# SCH_stewart-platform.net
KiCad netlist of a schematic drawn in EasyEDA
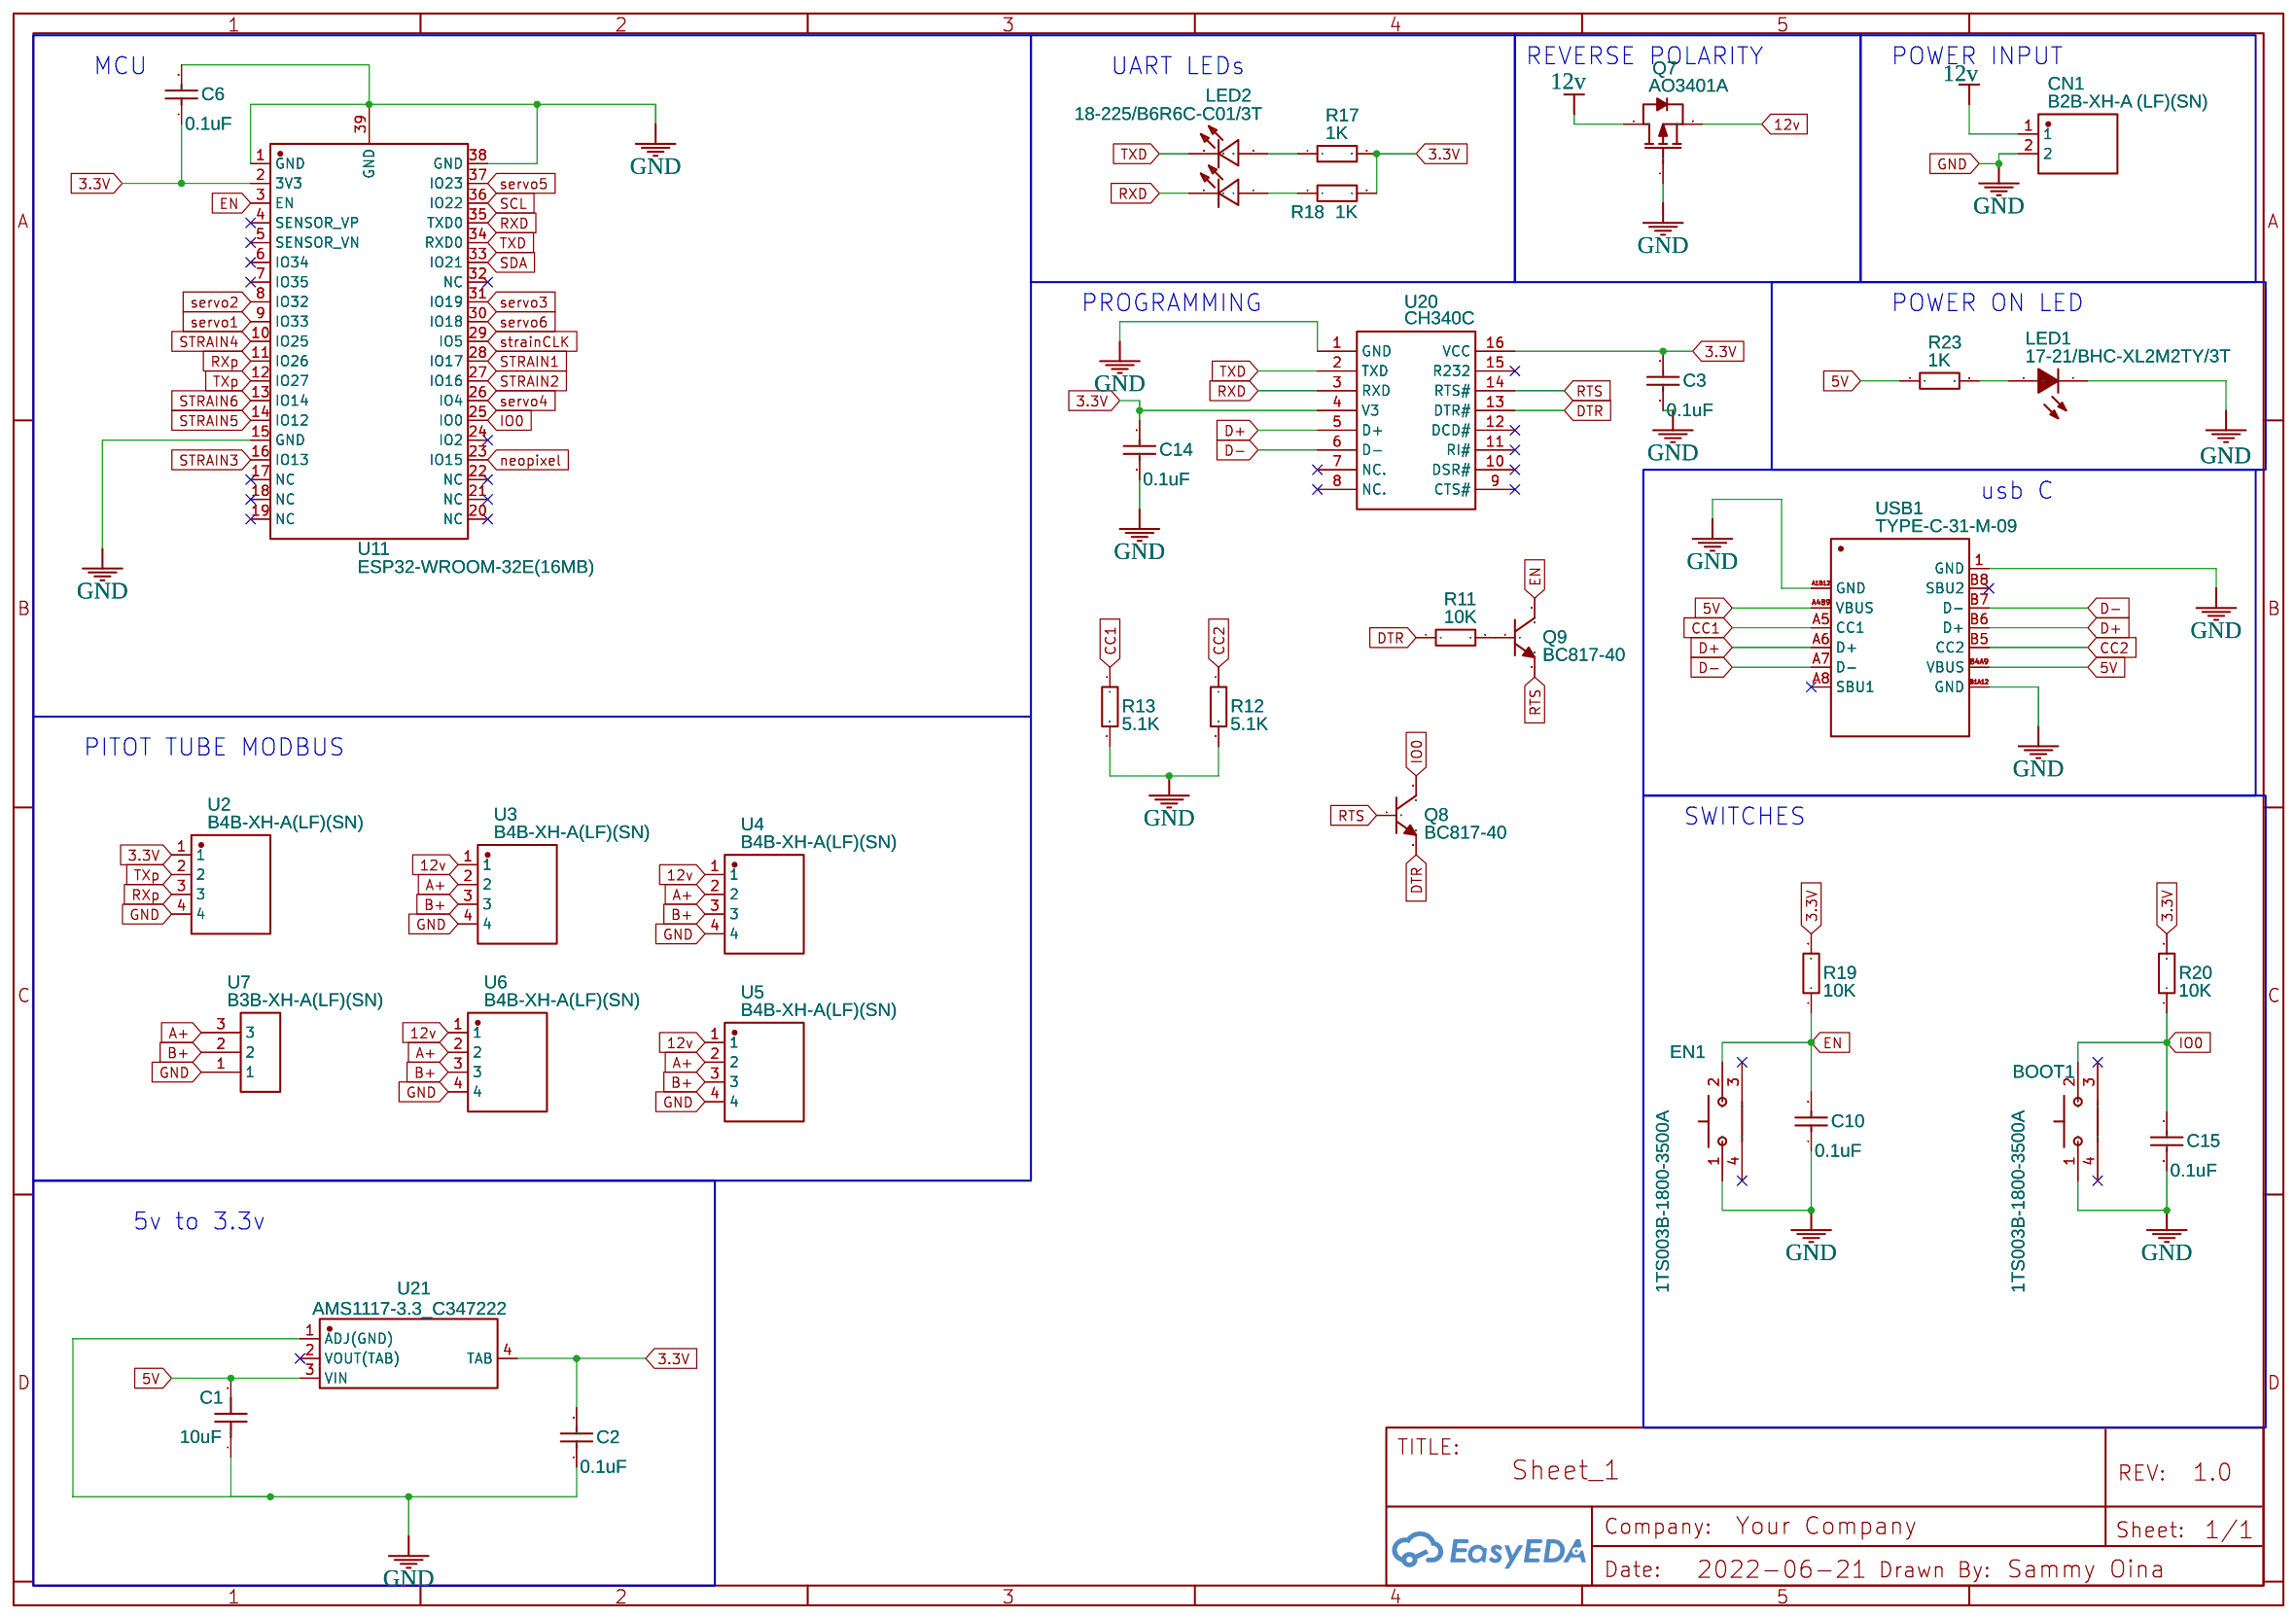
[diagram p0: Sheet_1]
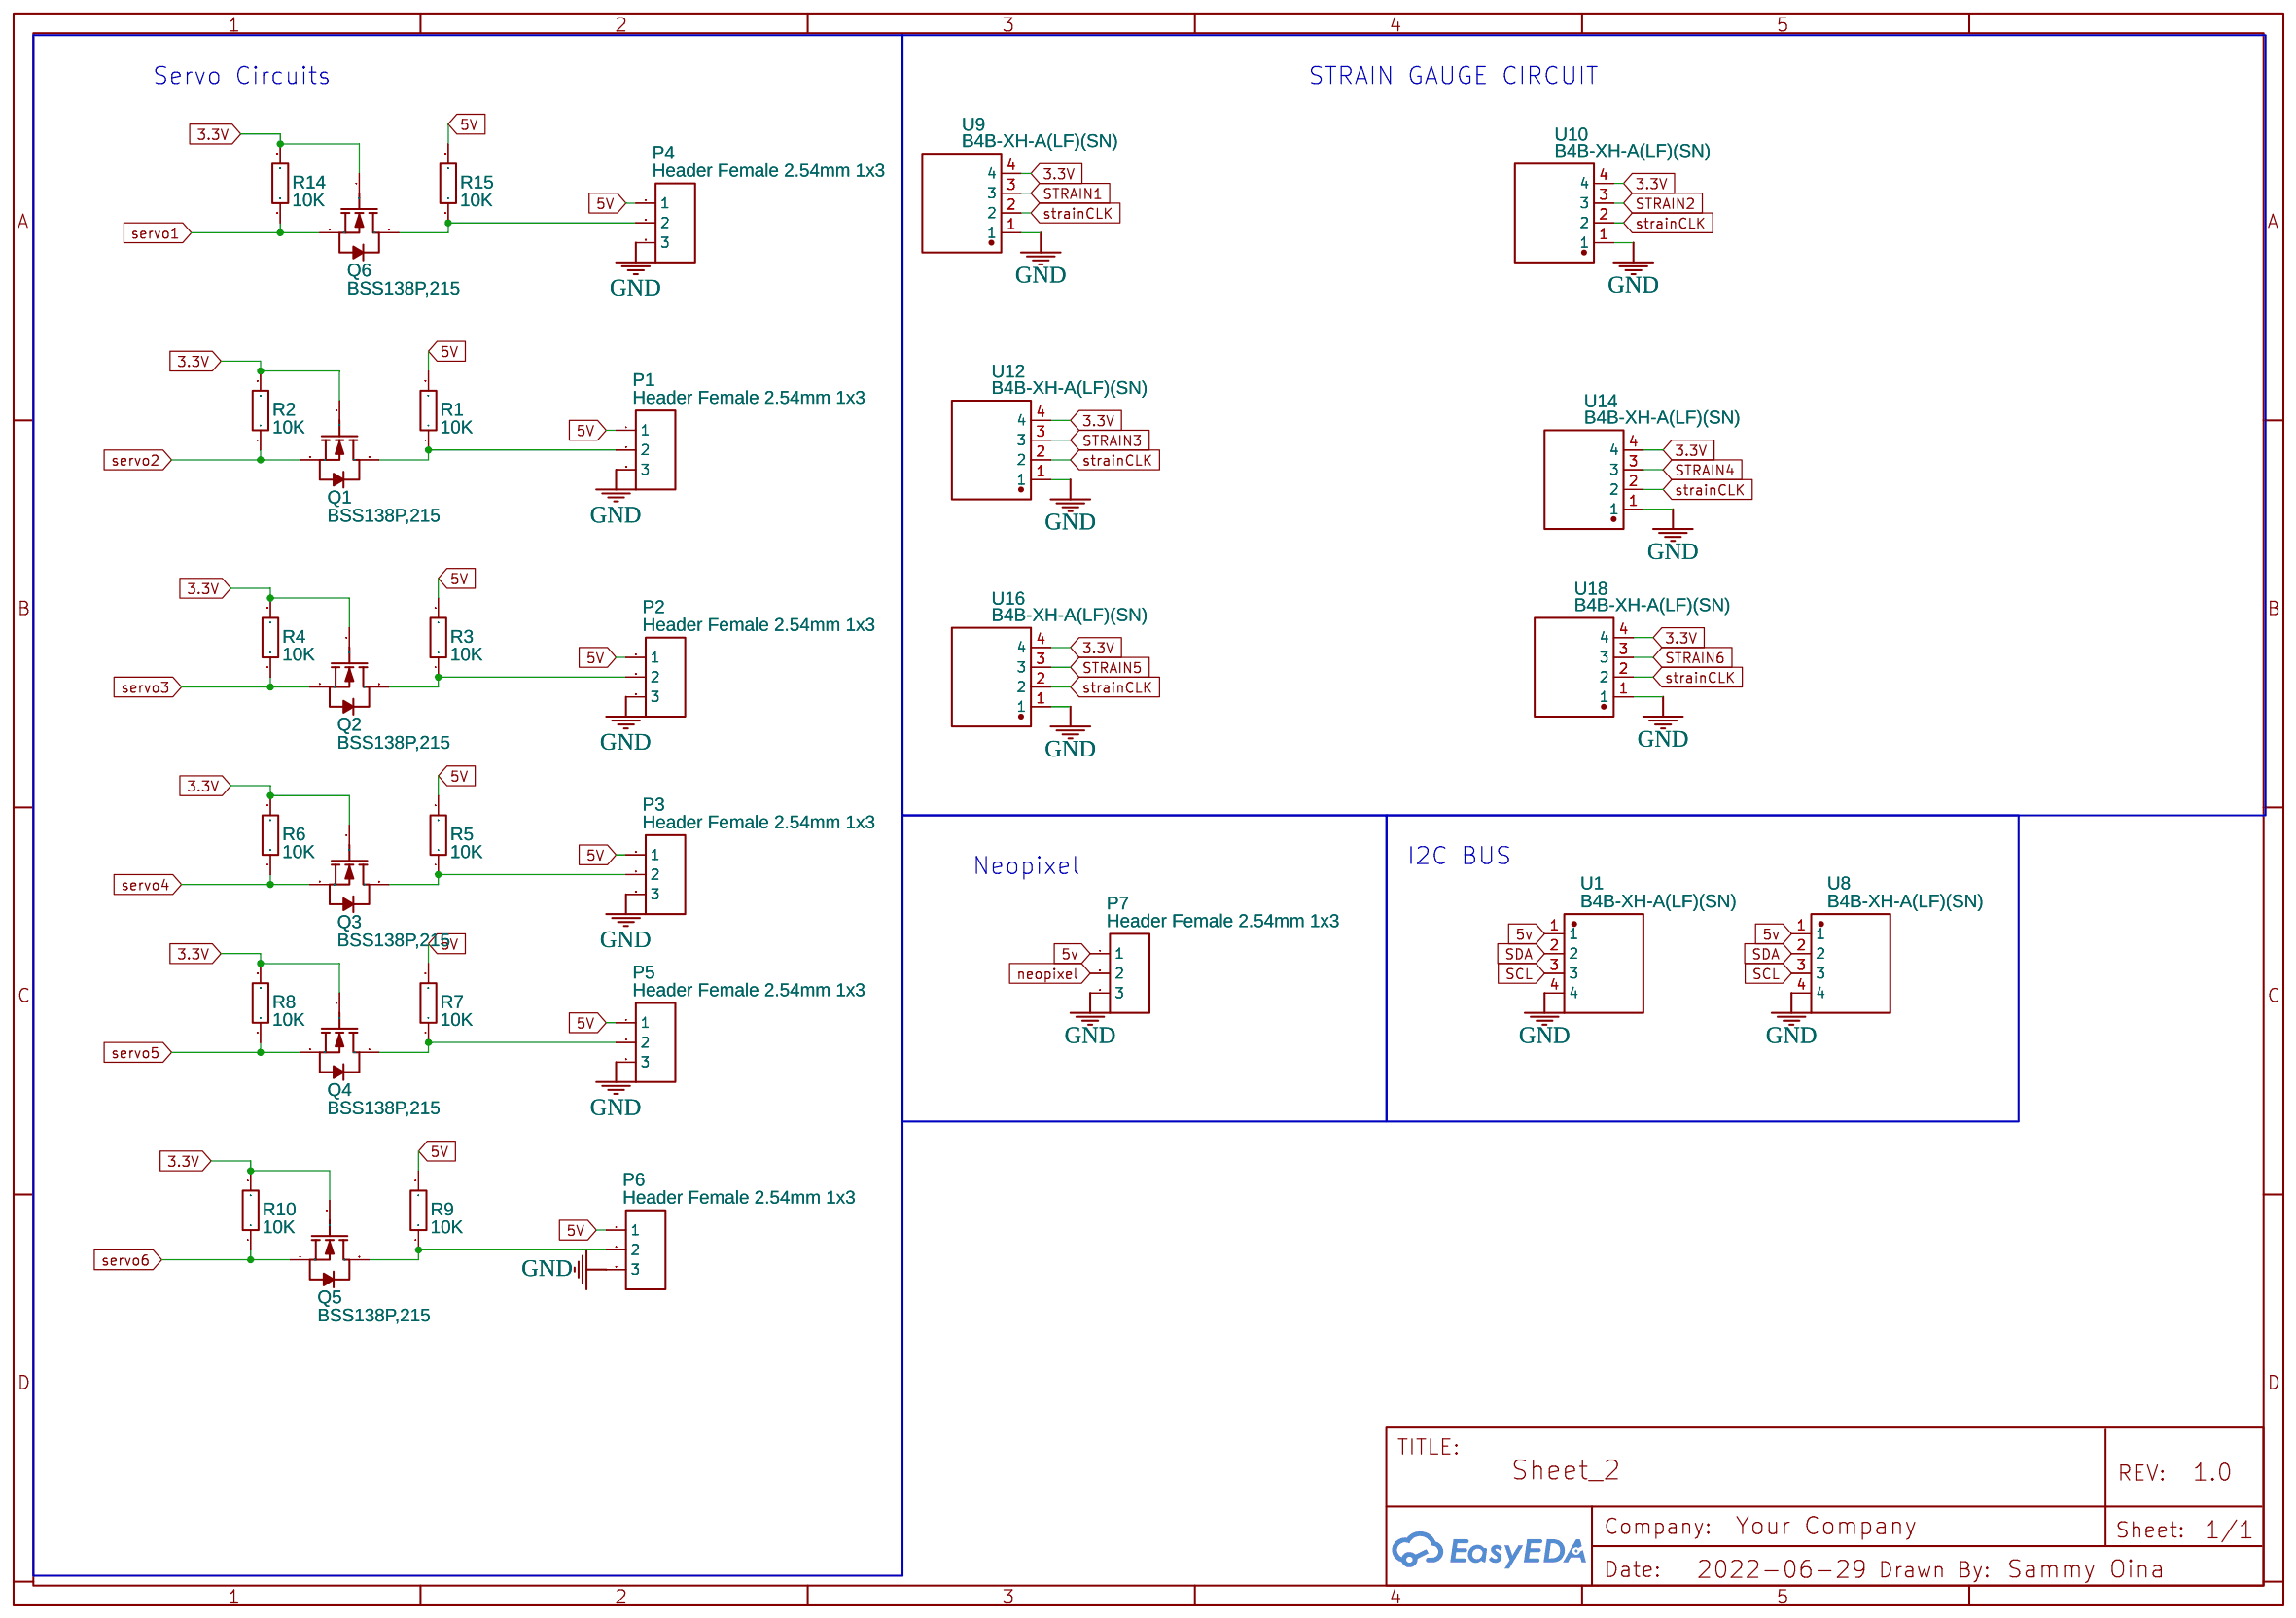
[diagram p1: Sheet_2]
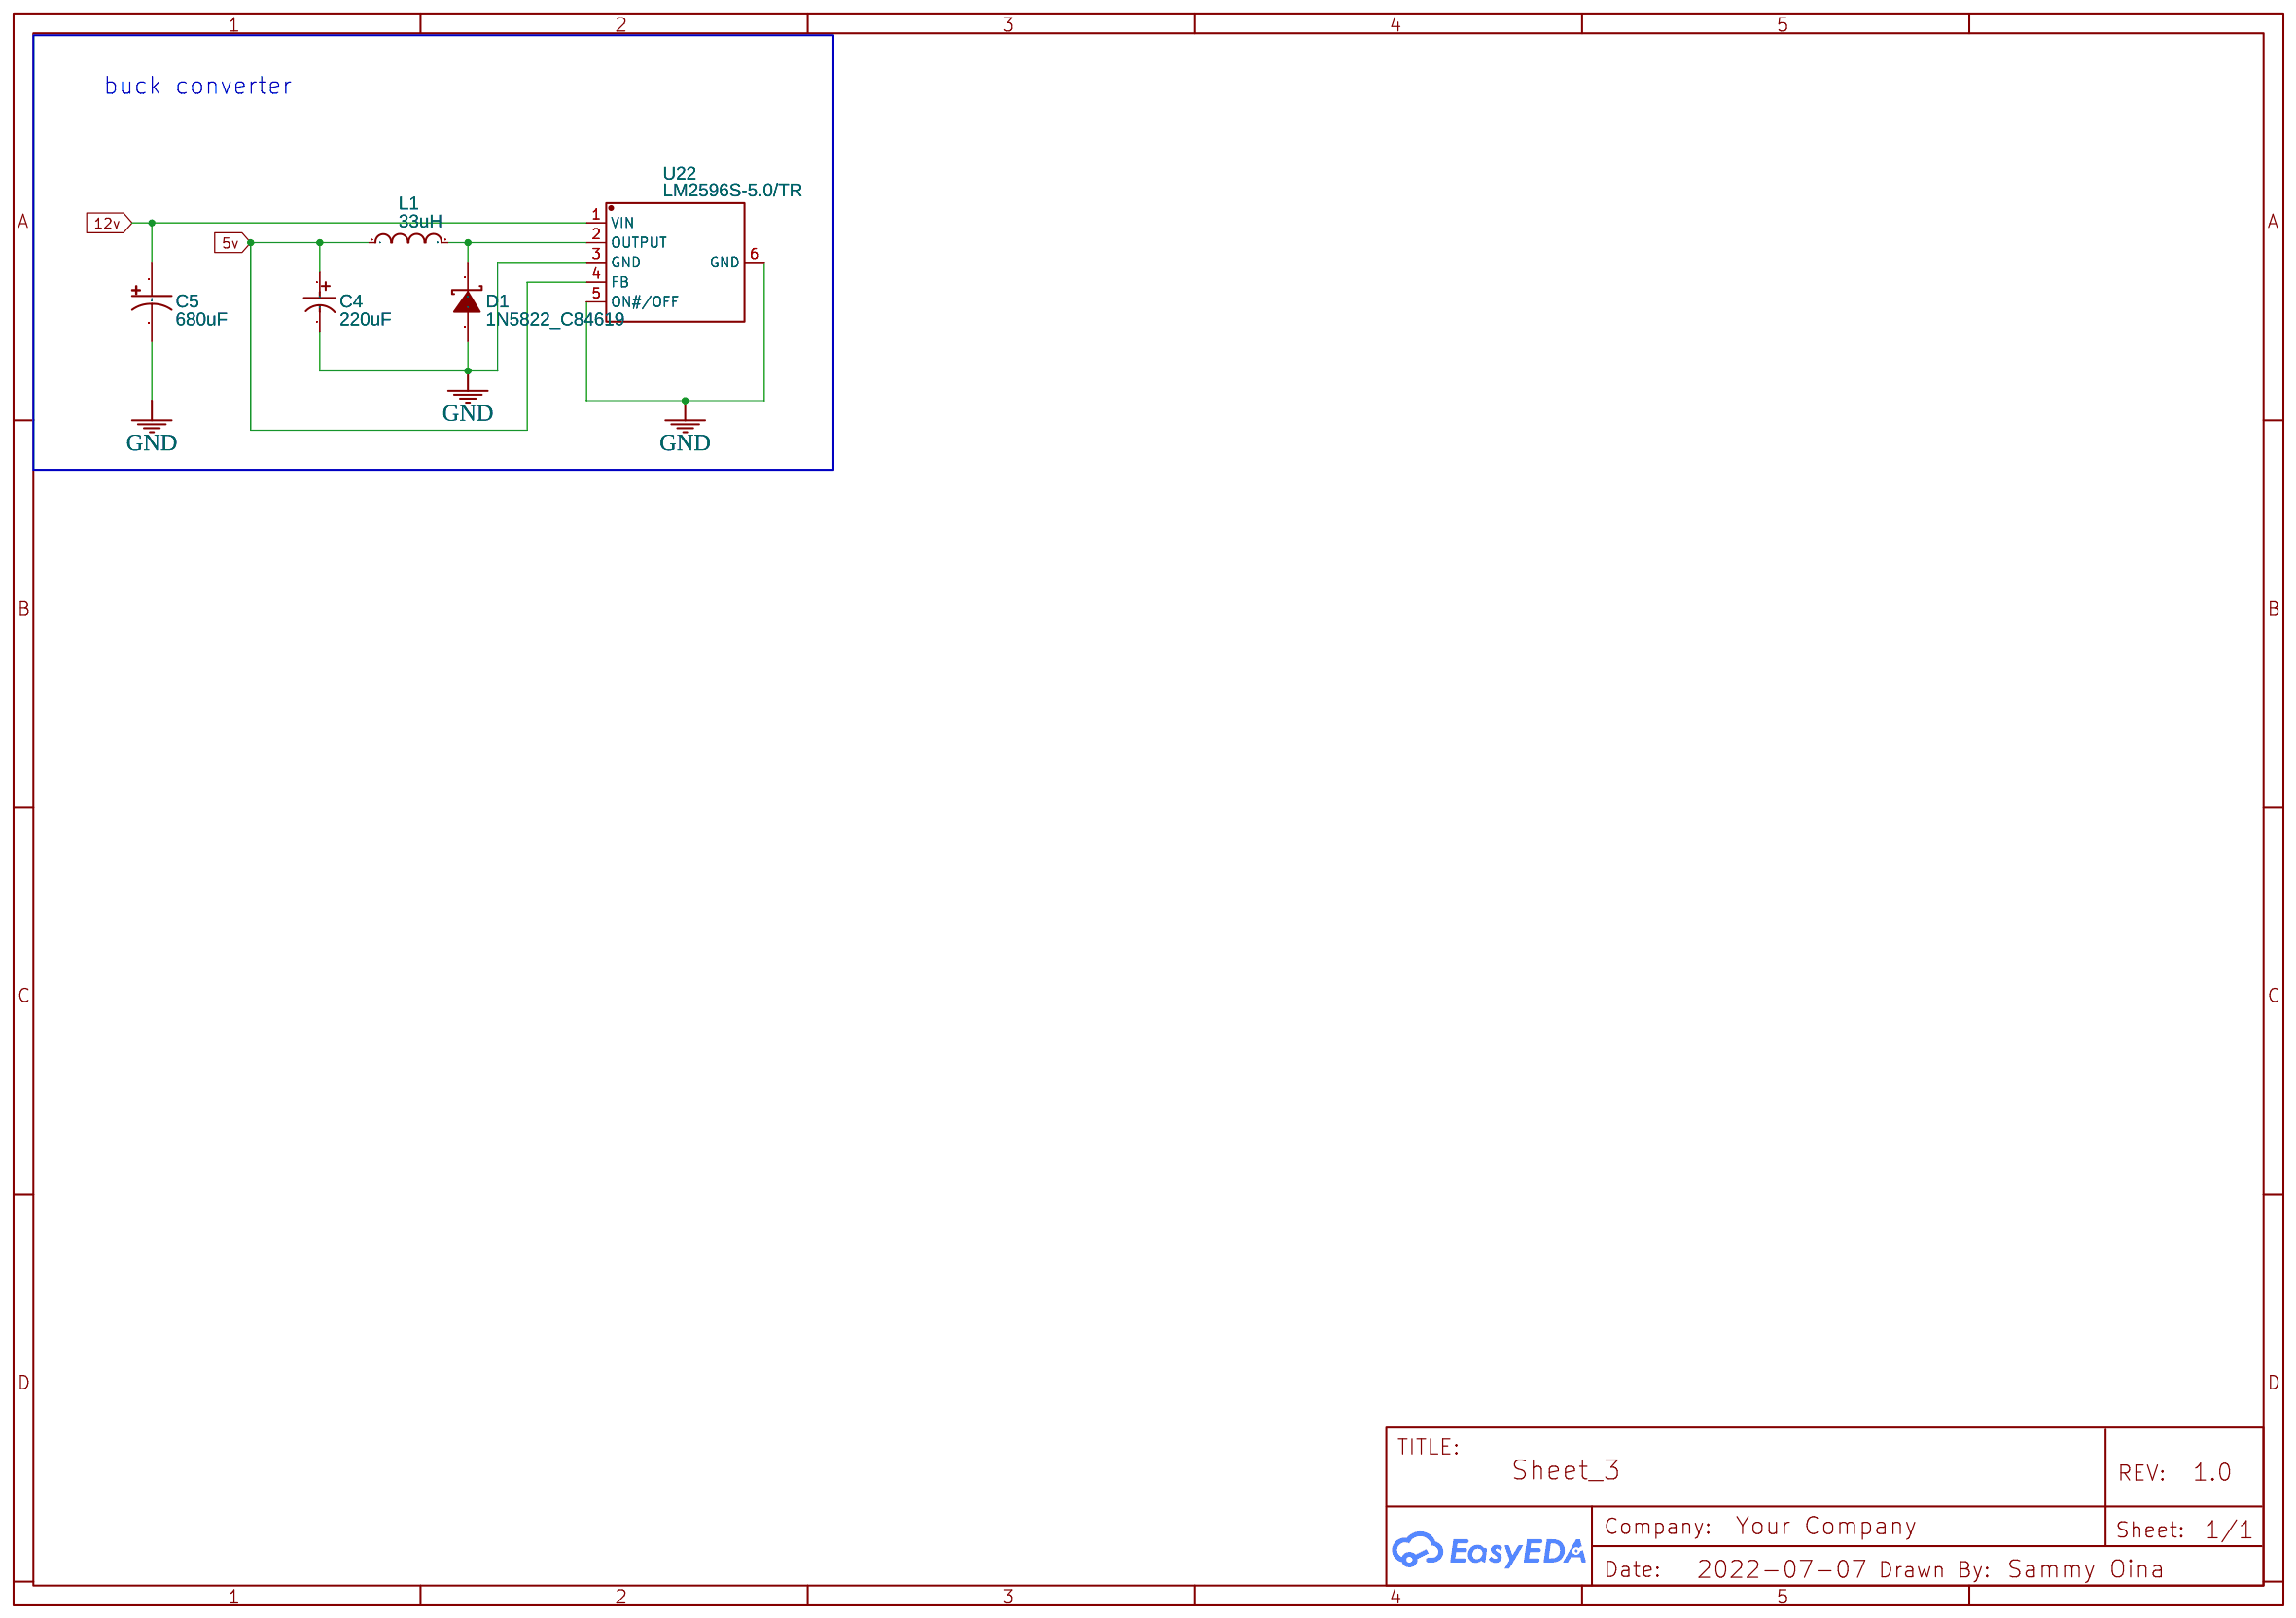
[diagram p2: Sheet_3]

(export (version "E")
  (design (tool "Eeschema 10.0.6"))
  (components
    (comp (ref "BOOT1")
      (value "1TS003B-1800-3500A")
      (fields (field (name "BOM_Supplier Part") "C255809"))
      (libsource (lib "") (part "1TS003B-1800-3500A_1"))
    )
    (comp (ref "C1")
      (value "10uF")
      (fields
        (field (name "BOM_Manufacturer Part") "CL05A106MQ8NUB8")
        (field (name "BOM_Supplier Part") "C307416")
      )
      (libsource (lib "") (part "CL05A106MQ8NUB8"))
    )
    (comp (ref "C2")
      (value "0.1uF")
      (fields
        (field (name "BOM_Manufacturer Part") "0603B104K250")
        (field (name "BOM_Supplier Part") "C83054")
      )
      (libsource (lib "") (part "0603B104K250"))
    )
    (comp (ref "C3")
      (value "0.1uF")
      (fields
        (field (name "BOM_Manufacturer Part") "0603B104K250")
        (field (name "BOM_Supplier Part") "C83054")
      )
      (libsource (lib "") (part "0603B104K250"))
    )
    (comp (ref "C6")
      (value "0.1uF")
      (fields
        (field (name "BOM_Manufacturer Part") "0603B104K250")
        (field (name "BOM_Supplier Part") "C83054")
      )
      (libsource (lib "") (part "0603B104K250"))
    )
    (comp (ref "C10")
      (value "0.1uF")
      (fields
        (field (name "BOM_Manufacturer Part") "0603B104K250")
        (field (name "BOM_Supplier Part") "C83054")
      )
      (libsource (lib "") (part "0603B104K250"))
    )
    (comp (ref "C14")
      (value "0.1uF")
      (fields
        (field (name "BOM_Manufacturer Part") "0603B104K250")
        (field (name "BOM_Supplier Part") "C83054")
      )
      (libsource (lib "") (part "0603B104K250"))
    )
    (comp (ref "C15")
      (value "0.1uF")
      (fields
        (field (name "BOM_Manufacturer Part") "0603B104K250")
        (field (name "BOM_Supplier Part") "C83054")
      )
      (libsource (lib "") (part "0603B104K250"))
    )
    (comp (ref "CN1")
      (value "B2B-XH-A (LF)(SN)")
      (fields (field (name "BOM_Supplier Part") "C158012"))
      (libsource (lib "") (part "B2B-XH-A (LF)(SN)"))
    )
    (comp (ref "EN1")
      (value "1TS003B-1800-3500A")
      (fields (field (name "BOM_Supplier Part") "C255809"))
      (libsource (lib "") (part "1TS003B-1800-3500A"))
    )
    (comp (ref "LED1")
      (value "17-21/BHC-XL2M2TY/3T")
      (fields (field (name "BOM_Supplier Part") "C72035"))
      (libsource (lib "") (part "17-21/BHC-XL2M2TY/3T"))
    )
    (comp (ref "LED2")
      (value "18-225/B6R6C-C01/3T")
      (fields (field (name "BOM_Supplier Part") "C282127"))
      (libsource (lib "") (part "18-225/B6R6C-C01/3T"))
    )
    (comp (ref "Q7")
      (value "AO3401A")
      (fields (field (name "BOM_Supplier Part") "C15127"))
      (libsource (lib "") (part "AO3401A"))
    )
    (comp (ref "Q8")
      (value "BC817-40")
      (fields (field (name "BOM_Supplier Part") "C181151"))
      (libsource (lib "") (part "BC817-40"))
    )
    (comp (ref "Q9")
      (value "BC817-40")
      (fields (field (name "BOM_Supplier Part") "C181151"))
      (libsource (lib "") (part "BC817-40"))
    )
    (comp (ref "R11")
      (value "10K")
      (fields
        (field (name "BOM_Manufacturer Part") "0402WGJ0103TCE")
        (field (name "BOM_Supplier Part") "C25531")
      )
      (libsource (lib "") (part "0402WGJ0103TCE"))
    )
    (comp (ref "R12")
      (value "5.1K")
      (fields
        (field (name "BOM_Manufacturer Part") "0402WGF5101TCE")
        (field (name "BOM_Supplier Part") "C25905")
      )
      (libsource (lib "") (part "0402WGF5101TCE"))
    )
    (comp (ref "R13")
      (value "5.1K")
      (fields
        (field (name "BOM_Manufacturer Part") "0402WGF5101TCE")
        (field (name "BOM_Supplier Part") "C25905")
      )
      (libsource (lib "") (part "0402WGF5101TCE"))
    )
    (comp (ref "R17")
      (value "1K")
      (fields
        (field (name "BOM_Manufacturer Part") "PTFR0805B1K00N9")
        (field (name "BOM_Supplier Part") "C328437")
      )
      (libsource (lib "") (part "PTFR0805B1K00N9"))
    )
    (comp (ref "R18")
      (value "1K")
      (fields
        (field (name "BOM_Manufacturer Part") "PTFR0805B1K00N9")
        (field (name "BOM_Supplier Part") "C328437")
      )
      (libsource (lib "") (part "PTFR0805B1K00N9"))
    )
    (comp (ref "R19")
      (value "10K")
      (fields
        (field (name "BOM_Manufacturer Part") "0402WGJ0103TCE")
        (field (name "BOM_Supplier Part") "C25531")
      )
      (libsource (lib "") (part "0402WGJ0103TCE_1"))
    )
    (comp (ref "R20")
      (value "10K")
      (fields
        (field (name "BOM_Manufacturer Part") "0402WGJ0103TCE")
        (field (name "BOM_Supplier Part") "C25531")
      )
      (libsource (lib "") (part "0402WGJ0103TCE_1"))
    )
    (comp (ref "R23")
      (value "1K")
      (fields
        (field (name "BOM_Manufacturer Part") "PTFR0805B1K00N9")
        (field (name "BOM_Supplier Part") "C328437")
      )
      (libsource (lib "") (part "PTFR0805B1K00N9"))
    )
    (comp (ref "U2")
      (value "B4B-XH-A(LF)(SN)")
      (fields (field (name "BOM_Supplier Part") "C144395"))
      (libsource (lib "") (part "B4B-XH-A(LF)(SN)"))
    )
    (comp (ref "U3")
      (value "B4B-XH-A(LF)(SN)")
      (fields (field (name "BOM_Supplier Part") "C144395"))
      (libsource (lib "") (part "B4B-XH-A(LF)(SN)"))
    )
    (comp (ref "U4")
      (value "B4B-XH-A(LF)(SN)")
      (fields (field (name "BOM_Supplier Part") "C144395"))
      (libsource (lib "") (part "B4B-XH-A(LF)(SN)"))
    )
    (comp (ref "U5")
      (value "B4B-XH-A(LF)(SN)")
      (fields (field (name "BOM_Supplier Part") "C144395"))
      (libsource (lib "") (part "B4B-XH-A(LF)(SN)"))
    )
    (comp (ref "U6")
      (value "B4B-XH-A(LF)(SN)")
      (fields (field (name "BOM_Supplier Part") "C144395"))
      (libsource (lib "") (part "B4B-XH-A(LF)(SN)"))
    )
    (comp (ref "U7")
      (value "B3B-XH-A(LF)(SN)")
      (fields (field (name "BOM_Supplier Part") "C144394"))
      (libsource (lib "") (part "B3B-XH-A(LF)(SN)"))
    )
    (comp (ref "U11")
      (value "ESP32-WROOM-32E(16MB)")
      (fields (field (name "BOM_Supplier Part") "C701343"))
      (libsource (lib "") (part "ESP32-WROOM-32E(16MB)"))
    )
    (comp (ref "U20")
      (value "CH340C")
      (fields (field (name "BOM_Supplier Part") "C84681"))
      (libsource (lib "") (part "CH340C"))
    )
    (comp (ref "U21")
      (value "AMS1117-3.3_C347222")
      (fields
        (field (name "BOM_Manufacturer Part") "AMS1117-3.3")
        (field (name "BOM_Supplier Part") "C347222")
      )
      (libsource (lib "") (part "AMS1117-3.3_C347222"))
    )
    (comp (ref "USB1")
      (value "TYPE-C-31-M-09")
      (fields (field (name "BOM_Supplier Part") "C2689967"))
      (libsource (lib "") (part "TYPE-C-31-M-09"))
    )
    (comp (ref "P1")
      (value "Header Female 2.54mm 1x3")
      (fields
        (field (name "BOM_Manufacturer Part") "Header-Female-2.54_1x3")
        (field (name "BOM_Supplier Part") "C146243")
      )
      (libsource (lib "") (part "Header Female 2.54mm 1x3"))
    )
    (comp (ref "P2")
      (value "Header Female 2.54mm 1x3")
      (fields
        (field (name "BOM_Manufacturer Part") "Header-Female-2.54_1x3")
        (field (name "BOM_Supplier Part") "C146243")
      )
      (libsource (lib "") (part "Header Female 2.54mm 1x3"))
    )
    (comp (ref "P3")
      (value "Header Female 2.54mm 1x3")
      (fields
        (field (name "BOM_Manufacturer Part") "Header-Female-2.54_1x3")
        (field (name "BOM_Supplier Part") "C146243")
      )
      (libsource (lib "") (part "Header Female 2.54mm 1x3"))
    )
    (comp (ref "P4")
      (value "Header Female 2.54mm 1x3")
      (fields
        (field (name "BOM_Manufacturer Part") "Header-Female-2.54_1x3")
        (field (name "BOM_Supplier Part") "C146243")
      )
      (libsource (lib "") (part "Header Female 2.54mm 1x3"))
    )
    (comp (ref "P5")
      (value "Header Female 2.54mm 1x3")
      (fields
        (field (name "BOM_Manufacturer Part") "Header-Female-2.54_1x3")
        (field (name "BOM_Supplier Part") "C146243")
      )
      (libsource (lib "") (part "Header Female 2.54mm 1x3"))
    )
    (comp (ref "P6")
      (value "Header Female 2.54mm 1x3")
      (fields
        (field (name "BOM_Manufacturer Part") "Header-Female-2.54_1x3")
        (field (name "BOM_Supplier Part") "C146243")
      )
      (libsource (lib "") (part "Header Female 2.54mm 1x3"))
    )
    (comp (ref "P7")
      (value "Header Female 2.54mm 1x3")
      (fields
        (field (name "BOM_Manufacturer Part") "Header-Female-2.54_1x3")
        (field (name "BOM_Supplier Part") "C146243")
      )
      (libsource (lib "") (part "Header Female 2.54mm 1x3"))
    )
    (comp (ref "Q1")
      (value "BSS138P,215")
      (fields (field (name "BOM_Supplier Part") "C75547"))
      (libsource (lib "") (part "BSS138P,215"))
    )
    (comp (ref "Q2")
      (value "BSS138P,215")
      (fields (field (name "BOM_Supplier Part") "C75547"))
      (libsource (lib "") (part "BSS138P,215"))
    )
    (comp (ref "Q3")
      (value "BSS138P,215")
      (fields (field (name "BOM_Supplier Part") "C75547"))
      (libsource (lib "") (part "BSS138P,215"))
    )
    (comp (ref "Q4")
      (value "BSS138P,215")
      (fields (field (name "BOM_Supplier Part") "C75547"))
      (libsource (lib "") (part "BSS138P,215"))
    )
    (comp (ref "Q5")
      (value "BSS138P,215")
      (fields (field (name "BOM_Supplier Part") "C75547"))
      (libsource (lib "") (part "BSS138P,215"))
    )
    (comp (ref "Q6")
      (value "BSS138P,215")
      (fields (field (name "BOM_Supplier Part") "C75547"))
      (libsource (lib "") (part "BSS138P,215"))
    )
    (comp (ref "R1")
      (value "10K")
      (fields
        (field (name "BOM_Manufacturer Part") "0603WAF4701T5E")
        (field (name "BOM_Supplier Part") "C23162")
      )
      (libsource (lib "") (part "0603WAF4701T5E"))
    )
    (comp (ref "R2")
      (value "10K")
      (fields
        (field (name "BOM_Manufacturer Part") "0603WAF4701T5E")
        (field (name "BOM_Supplier Part") "C23162")
      )
      (libsource (lib "") (part "0603WAF4701T5E"))
    )
    (comp (ref "R3")
      (value "10K")
      (fields
        (field (name "BOM_Manufacturer Part") "0603WAF4701T5E")
        (field (name "BOM_Supplier Part") "C23162")
      )
      (libsource (lib "") (part "0603WAF4701T5E"))
    )
    (comp (ref "R4")
      (value "10K")
      (fields
        (field (name "BOM_Manufacturer Part") "0603WAF4701T5E")
        (field (name "BOM_Supplier Part") "C23162")
      )
      (libsource (lib "") (part "0603WAF4701T5E"))
    )
    (comp (ref "R5")
      (value "10K")
      (fields
        (field (name "BOM_Manufacturer Part") "0603WAF4701T5E")
        (field (name "BOM_Supplier Part") "C23162")
      )
      (libsource (lib "") (part "0603WAF4701T5E"))
    )
    (comp (ref "R6")
      (value "10K")
      (fields
        (field (name "BOM_Manufacturer Part") "0603WAF4701T5E")
        (field (name "BOM_Supplier Part") "C23162")
      )
      (libsource (lib "") (part "0603WAF4701T5E"))
    )
    (comp (ref "R7")
      (value "10K")
      (fields
        (field (name "BOM_Manufacturer Part") "0603WAF4701T5E")
        (field (name "BOM_Supplier Part") "C23162")
      )
      (libsource (lib "") (part "0603WAF4701T5E"))
    )
    (comp (ref "R8")
      (value "10K")
      (fields
        (field (name "BOM_Manufacturer Part") "0603WAF4701T5E")
        (field (name "BOM_Supplier Part") "C23162")
      )
      (libsource (lib "") (part "0603WAF4701T5E"))
    )
    (comp (ref "R9")
      (value "10K")
      (fields
        (field (name "BOM_Manufacturer Part") "0603WAF4701T5E")
        (field (name "BOM_Supplier Part") "C23162")
      )
      (libsource (lib "") (part "0603WAF4701T5E"))
    )
    (comp (ref "R10")
      (value "10K")
      (fields
        (field (name "BOM_Manufacturer Part") "0603WAF4701T5E")
        (field (name "BOM_Supplier Part") "C23162")
      )
      (libsource (lib "") (part "0603WAF4701T5E"))
    )
    (comp (ref "R14")
      (value "10K")
      (fields
        (field (name "BOM_Manufacturer Part") "0603WAF4701T5E")
        (field (name "BOM_Supplier Part") "C23162")
      )
      (libsource (lib "") (part "0603WAF4701T5E"))
    )
    (comp (ref "R15")
      (value "10K")
      (fields
        (field (name "BOM_Manufacturer Part") "0603WAF4701T5E")
        (field (name "BOM_Supplier Part") "C23162")
      )
      (libsource (lib "") (part "0603WAF4701T5E"))
    )
    (comp (ref "U1")
      (value "B4B-XH-A(LF)(SN)")
      (fields (field (name "BOM_Supplier Part") "C144395"))
      (libsource (lib "") (part "B4B-XH-A(LF)(SN)_1"))
    )
    (comp (ref "U8")
      (value "B4B-XH-A(LF)(SN)")
      (fields (field (name "BOM_Supplier Part") "C144395"))
      (libsource (lib "") (part "B4B-XH-A(LF)(SN)_1"))
    )
    (comp (ref "U9")
      (value "B4B-XH-A(LF)(SN)")
      (fields (field (name "BOM_Supplier Part") "C144395"))
      (libsource (lib "") (part "B4B-XH-A(LF)(SN)"))
    )
    (comp (ref "U10")
      (value "B4B-XH-A(LF)(SN)")
      (fields (field (name "BOM_Supplier Part") "C144395"))
      (libsource (lib "") (part "B4B-XH-A(LF)(SN)"))
    )
    (comp (ref "U12")
      (value "B4B-XH-A(LF)(SN)")
      (fields (field (name "BOM_Supplier Part") "C144395"))
      (libsource (lib "") (part "B4B-XH-A(LF)(SN)"))
    )
    (comp (ref "U14")
      (value "B4B-XH-A(LF)(SN)")
      (fields (field (name "BOM_Supplier Part") "C144395"))
      (libsource (lib "") (part "B4B-XH-A(LF)(SN)"))
    )
    (comp (ref "U16")
      (value "B4B-XH-A(LF)(SN)")
      (fields (field (name "BOM_Supplier Part") "C144395"))
      (libsource (lib "") (part "B4B-XH-A(LF)(SN)"))
    )
    (comp (ref "U18")
      (value "B4B-XH-A(LF)(SN)")
      (fields (field (name "BOM_Supplier Part") "C144395"))
      (libsource (lib "") (part "B4B-XH-A(LF)(SN)"))
    )
    (comp (ref "C4")
      (value "220uF")
      (fields
        (field (name "BOM_Manufacturer Part") "UCD1H221MNL1GS")
        (field (name "BOM_Supplier Part") "C116211")
      )
      (libsource (lib "") (part "UCD1H221MNL1GS"))
    )
    (comp (ref "C5")
      (value "680uF")
      (fields
        (field (name "BOM_Manufacturer Part") "VEJ681M1CTR-1010")
        (field (name "BOM_Supplier Part") "C134782")
      )
      (libsource (lib "") (part "VEJ681M1CTR-1010"))
    )
    (comp (ref "D1")
      (value "1N5822_C84619")
      (fields (field (name "BOM_Manufacturer Part") "1N5822") (field (name "BOM_Supplier Part") "C84619"))
      (libsource (lib "") (part "1N5822_C84619"))
    )
    (comp (ref "L1")
      (value "33uH")
      (fields
        (field (name "BOM_Manufacturer Part") "MCW-0630-330-N2")
        (field (name "BOM_Supplier Part") "C177254")
      )
      (libsource (lib "") (part "MCW-0630-330-N2"))
    )
    (comp (ref "U22")
      (value "LM2596S-5.0/TR")
      (fields (field (name "BOM_Supplier Part") "C194349"))
      (libsource (lib "") (part "LM2596S-5.0/TR"))
    )
  )
  (nets
    (net (code "1") (name "3.3V") (class "Default")
      (node (ref "C14") (pin "2") (pinfunction "2_2") (pintype "input"))
      (node (ref "C2") (pin "2") (pinfunction "2_2") (pintype "input"))
      (node (ref "C3") (pin "2") (pinfunction "2_2") (pintype "input"))
      (node (ref "C6") (pin "1") (pinfunction "1_1") (pintype "input"))
      (node (ref "Q1") (pin "1") (pinfunction "G_1") (pintype "unspecified"))
      (node (ref "Q2") (pin "1") (pinfunction "G_1") (pintype "unspecified"))
      (node (ref "Q3") (pin "1") (pinfunction "G_1") (pintype "unspecified"))
      (node (ref "Q4") (pin "1") (pinfunction "G_1") (pintype "unspecified"))
      (node (ref "Q5") (pin "1") (pinfunction "G_1") (pintype "unspecified"))
      (node (ref "Q6") (pin "1") (pinfunction "G_1") (pintype "unspecified"))
      (node (ref "R10") (pin "2") (pinfunction "2_2") (pintype "input"))
      (node (ref "R14") (pin "2") (pinfunction "2_2") (pintype "input"))
      (node (ref "R17") (pin "2") (pinfunction "2_2") (pintype "unspecified"))
      (node (ref "R18") (pin "2") (pinfunction "2_2") (pintype "unspecified"))
      (node (ref "R19") (pin "2") (pinfunction "2_2") (pintype "input"))
      (node (ref "R2") (pin "2") (pinfunction "2_2") (pintype "input"))
      (node (ref "R20") (pin "2") (pinfunction "2_2") (pintype "input"))
      (node (ref "R4") (pin "2") (pinfunction "2_2") (pintype "input"))
      (node (ref "R6") (pin "2") (pinfunction "2_2") (pintype "input"))
      (node (ref "R8") (pin "2") (pinfunction "2_2") (pintype "input"))
      (node (ref "U10") (pin "4") (pinfunction "4_4") (pintype "unspecified"))
      (node (ref "U11") (pin "2") (pinfunction "3V3_2") (pintype "unspecified"))
      (node (ref "U12") (pin "4") (pinfunction "4_4") (pintype "unspecified"))
      (node (ref "U14") (pin "4") (pinfunction "4_4") (pintype "unspecified"))
      (node (ref "U16") (pin "4") (pinfunction "4_4") (pintype "unspecified"))
      (node (ref "U18") (pin "4") (pinfunction "4_4") (pintype "unspecified"))
      (node (ref "U2") (pin "1") (pinfunction "1_1") (pintype "unspecified"))
      (node (ref "U20") (pin "16") (pinfunction "VCC_16") (pintype "unspecified"))
      (node (ref "U20") (pin "4") (pinfunction "V3_4") (pintype "unspecified"))
      (node (ref "U21") (pin "4") (pinfunction "TAB_4") (pintype "unspecified"))
      (node (ref "U9") (pin "4") (pinfunction "4_4") (pintype "unspecified"))
    )
    (net (code "2") (name "5V") (class "Default")
      (node (ref "C1") (pin "2") (pinfunction "2_2") (pintype "unspecified"))
      (node (ref "P1") (pin "1") (pinfunction "1_1") (pintype "input"))
      (node (ref "P2") (pin "1") (pinfunction "1_1") (pintype "input"))
      (node (ref "P3") (pin "1") (pinfunction "1_1") (pintype "input"))
      (node (ref "P4") (pin "1") (pinfunction "1_1") (pintype "input"))
      (node (ref "P5") (pin "1") (pinfunction "1_1") (pintype "input"))
      (node (ref "P6") (pin "1") (pinfunction "1_1") (pintype "input"))
      (node (ref "R1") (pin "2") (pinfunction "2_2") (pintype "input"))
      (node (ref "R15") (pin "2") (pinfunction "2_2") (pintype "input"))
      (node (ref "R23") (pin "1") (pinfunction "1_1") (pintype "unspecified"))
      (node (ref "R3") (pin "2") (pinfunction "2_2") (pintype "input"))
      (node (ref "R5") (pin "2") (pinfunction "2_2") (pintype "input"))
      (node (ref "R7") (pin "2") (pinfunction "2_2") (pintype "input"))
      (node (ref "R9") (pin "2") (pinfunction "2_2") (pintype "input"))
      (node (ref "U21") (pin "3") (pinfunction "VIN_3") (pintype "unspecified"))
      (node (ref "USB1") (pin "A4B9") (pinfunction "VBUS_A4B9") (pintype "unspecified"))
      (node (ref "USB1") (pin "B4A9") (pinfunction "VBUS_B4A9") (pintype "unspecified"))
    )
    (net (code "3") (name "5v") (class "Default")
      (node (ref "C4") (pin "1") (pinfunction "1_1") (pintype "input"))
      (node (ref "L1") (pin "1") (pinfunction "1_1") (pintype "unspecified"))
      (node (ref "P7") (pin "1") (pinfunction "1_1") (pintype "input"))
      (node (ref "U1") (pin "1") (pinfunction "1_1") (pintype "unspecified"))
      (node (ref "U22") (pin "4") (pinfunction "FB_4") (pintype "unspecified"))
      (node (ref "U8") (pin "1") (pinfunction "1_1") (pintype "unspecified"))
    )
    (net (code "4") (name "12v") (class "Default")
      (node (ref "C5") (pin "1") (pinfunction "1_1") (pintype "unspecified"))
      (node (ref "CN1") (pin "1") (pinfunction "1_1") (pintype "unspecified"))
      (node (ref "Q7") (pin "2") (pinfunction "S_2") (pintype "unspecified"))
      (node (ref "Q7") (pin "3") (pinfunction "D_3") (pintype "unspecified"))
      (node (ref "U22") (pin "1") (pinfunction "VIN_1") (pintype "unspecified"))
      (node (ref "U3") (pin "1") (pinfunction "1_1") (pintype "unspecified"))
      (node (ref "U4") (pin "1") (pinfunction "1_1") (pintype "unspecified"))
      (node (ref "U5") (pin "1") (pinfunction "1_1") (pintype "unspecified"))
      (node (ref "U6") (pin "1") (pinfunction "1_1") (pintype "unspecified"))
    )
    (net (code "5") (name "A+") (class "Default")
      (node (ref "U3") (pin "2") (pinfunction "2_2") (pintype "unspecified"))
      (node (ref "U4") (pin "2") (pinfunction "2_2") (pintype "unspecified"))
      (node (ref "U5") (pin "2") (pinfunction "2_2") (pintype "unspecified"))
      (node (ref "U6") (pin "2") (pinfunction "2_2") (pintype "unspecified"))
      (node (ref "U7") (pin "3") (pinfunction "3_3") (pintype "unspecified"))
    )
    (net (code "6") (name "B+") (class "Default")
      (node (ref "U3") (pin "3") (pinfunction "3_3") (pintype "unspecified"))
      (node (ref "U4") (pin "3") (pinfunction "3_3") (pintype "unspecified"))
      (node (ref "U5") (pin "3") (pinfunction "3_3") (pintype "unspecified"))
      (node (ref "U6") (pin "3") (pinfunction "3_3") (pintype "unspecified"))
      (node (ref "U7") (pin "2") (pinfunction "2_2") (pintype "unspecified"))
    )
    (net (code "7") (name "CC1") (class "Default")
      (node (ref "R13") (pin "1") (pinfunction "1_1") (pintype "input"))
      (node (ref "USB1") (pin "A5") (pinfunction "CC1_A5") (pintype "unspecified"))
    )
    (net (code "8") (name "CC2") (class "Default")
      (node (ref "R12") (pin "1") (pinfunction "1_1") (pintype "input"))
      (node (ref "USB1") (pin "B5") (pinfunction "CC2_B5") (pintype "unspecified"))
    )
    (net (code "9") (name "D+") (class "Default")
      (node (ref "U20") (pin "5") (pinfunction "D+_5") (pintype "unspecified"))
      (node (ref "USB1") (pin "A6") (pinfunction "D+_A6") (pintype "unspecified"))
      (node (ref "USB1") (pin "B6") (pinfunction "D+_B6") (pintype "unspecified"))
    )
    (net (code "10") (name "D-") (class "Default")
      (node (ref "U20") (pin "6") (pinfunction "D-_6") (pintype "unspecified"))
      (node (ref "USB1") (pin "A7") (pinfunction "D-_A7") (pintype "unspecified"))
      (node (ref "USB1") (pin "B7") (pinfunction "D-_B7") (pintype "unspecified"))
    )
    (net (code "11") (name "DTR") (class "Default")
      (node (ref "Q8") (pin "2") (pinfunction "2_2") (pintype "input"))
      (node (ref "R11") (pin "1") (pinfunction "1_1") (pintype "input"))
      (node (ref "U20") (pin "13") (pinfunction "DTR#_13") (pintype "unspecified"))
    )
    (net (code "12") (name "EN") (class "Default")
      (node (ref "C10") (pin "2") (pinfunction "2_2") (pintype "input"))
      (node (ref "EN1") (pin "2") (pinfunction "2_2") (pintype "unspecified"))
      (node (ref "Q9") (pin "3") (pinfunction "3_3") (pintype "input"))
      (node (ref "R19") (pin "1") (pinfunction "1_1") (pintype "input"))
      (node (ref "U11") (pin "3") (pinfunction "EN_3") (pintype "unspecified"))
    )
    (net (code "13") (name "GND") (class "Default")
      (node (ref "BOOT1") (pin "1") (pinfunction "1_1") (pintype "unspecified"))
      (node (ref "C1") (pin "1") (pinfunction "1_1") (pintype "unspecified"))
      (node (ref "C10") (pin "1") (pinfunction "1_1") (pintype "input"))
      (node (ref "C14") (pin "1") (pinfunction "1_1") (pintype "input"))
      (node (ref "C15") (pin "1") (pinfunction "1_1") (pintype "input"))
      (node (ref "C2") (pin "1") (pinfunction "1_1") (pintype "input"))
      (node (ref "C3") (pin "1") (pinfunction "1_1") (pintype "input"))
      (node (ref "C4") (pin "2") (pinfunction "2_2") (pintype "input"))
      (node (ref "C5") (pin "2") (pinfunction "2_2") (pintype "unspecified"))
      (node (ref "C6") (pin "2") (pinfunction "2_2") (pintype "input"))
      (node (ref "CN1") (pin "2") (pinfunction "2_2") (pintype "unspecified"))
      (node (ref "D1") (pin "2") (pinfunction "A_2") (pintype "unspecified"))
      (node (ref "EN1") (pin "1") (pinfunction "1_1") (pintype "unspecified"))
      (node (ref "LED1") (pin "1") (pinfunction "-_1") (pintype "input"))
      (node (ref "P1") (pin "3") (pinfunction "3_3") (pintype "input"))
      (node (ref "P2") (pin "3") (pinfunction "3_3") (pintype "input"))
      (node (ref "P3") (pin "3") (pinfunction "3_3") (pintype "input"))
      (node (ref "P4") (pin "3") (pinfunction "3_3") (pintype "input"))
      (node (ref "P5") (pin "3") (pinfunction "3_3") (pintype "input"))
      (node (ref "P6") (pin "3") (pinfunction "3_3") (pintype "input"))
      (node (ref "P7") (pin "3") (pinfunction "3_3") (pintype "input"))
      (node (ref "Q7") (pin "1") (pinfunction "G_1") (pintype "unspecified"))
      (node (ref "R12") (pin "2") (pinfunction "2_2") (pintype "input"))
      (node (ref "R13") (pin "2") (pinfunction "2_2") (pintype "input"))
      (node (ref "U1") (pin "4") (pinfunction "4_4") (pintype "unspecified"))
      (node (ref "U10") (pin "1") (pinfunction "1_1") (pintype "unspecified"))
      (node (ref "U11") (pin "1") (pinfunction "GND_1") (pintype "unspecified"))
      (node (ref "U11") (pin "15") (pinfunction "GND_15") (pintype "unspecified"))
      (node (ref "U11") (pin "38") (pinfunction "GND_38") (pintype "unspecified"))
      (node (ref "U11") (pin "39") (pinfunction "GND_39") (pintype "unspecified"))
      (node (ref "U12") (pin "1") (pinfunction "1_1") (pintype "unspecified"))
      (node (ref "U14") (pin "1") (pinfunction "1_1") (pintype "unspecified"))
      (node (ref "U16") (pin "1") (pinfunction "1_1") (pintype "unspecified"))
      (node (ref "U18") (pin "1") (pinfunction "1_1") (pintype "unspecified"))
      (node (ref "U2") (pin "4") (pinfunction "4_4") (pintype "unspecified"))
      (node (ref "U20") (pin "1") (pinfunction "GND_1") (pintype "unspecified"))
      (node (ref "U21") (pin "1") (pinfunction "ADJ(GND)_1") (pintype "unspecified"))
      (node (ref "U22") (pin "3") (pinfunction "GND_3") (pintype "unspecified"))
      (node (ref "U22") (pin "5") (pinfunction "ON#/OFF_5") (pintype "unspecified"))
      (node (ref "U22") (pin "6") (pinfunction "GND_6") (pintype "unspecified"))
      (node (ref "U3") (pin "4") (pinfunction "4_4") (pintype "unspecified"))
      (node (ref "U4") (pin "4") (pinfunction "4_4") (pintype "unspecified"))
      (node (ref "U5") (pin "4") (pinfunction "4_4") (pintype "unspecified"))
      (node (ref "U6") (pin "4") (pinfunction "4_4") (pintype "unspecified"))
      (node (ref "U7") (pin "1") (pinfunction "1_1") (pintype "unspecified"))
      (node (ref "U8") (pin "4") (pinfunction "4_4") (pintype "unspecified"))
      (node (ref "U9") (pin "1") (pinfunction "1_1") (pintype "unspecified"))
      (node (ref "USB1") (pin "1") (pinfunction "GND_1") (pintype "unspecified"))
      (node (ref "USB1") (pin "A1B12") (pinfunction "GND_A1B12") (pintype "unspecified"))
      (node (ref "USB1") (pin "B1A12") (pinfunction "GND_B1A12") (pintype "unspecified"))
    )
    (net (code "14") (name "IO0") (class "Default")
      (node (ref "BOOT1") (pin "2") (pinfunction "2_2") (pintype "unspecified"))
      (node (ref "C15") (pin "2") (pinfunction "2_2") (pintype "input"))
      (node (ref "Q8") (pin "3") (pinfunction "3_3") (pintype "input"))
      (node (ref "R20") (pin "1") (pinfunction "1_1") (pintype "input"))
      (node (ref "U11") (pin "25") (pinfunction "IO0_25") (pintype "unspecified"))
    )
    (net (code "15") (name "Net-(D1-C)") (class "Default")
      (node (ref "D1") (pin "1") (pinfunction "C_1") (pintype "unspecified"))
      (node (ref "L1") (pin "2") (pinfunction "2_2") (pintype "unspecified"))
      (node (ref "U22") (pin "2") (pinfunction "OUTPUT_2") (pintype "unspecified"))
    )
    (net (code "16") (name "Net-(LED1-+)") (class "Default")
      (node (ref "LED1") (pin "2") (pinfunction "+_2") (pintype "input"))
      (node (ref "R23") (pin "2") (pinfunction "2_2") (pintype "unspecified"))
    )
    (net (code "17") (name "Net-(LED2-Pad1)") (class "Default")
      (node (ref "LED2") (pin "1") (pinfunction "1_1") (pintype "unspecified"))
      (node (ref "R18") (pin "1") (pinfunction "1_1") (pintype "unspecified"))
    )
    (net (code "18") (name "Net-(LED2-Pad2)") (class "Default")
      (node (ref "LED2") (pin "2") (pinfunction "2_2") (pintype "unspecified"))
      (node (ref "R17") (pin "1") (pinfunction "1_1") (pintype "unspecified"))
    )
    (net (code "19") (name "Net-(Q1-D)") (class "Default")
      (node (ref "P1") (pin "2") (pinfunction "2_2") (pintype "input"))
      (node (ref "Q1") (pin "3") (pinfunction "D_3") (pintype "unspecified"))
      (node (ref "R1") (pin "1") (pinfunction "1_1") (pintype "input"))
    )
    (net (code "20") (name "Net-(Q2-D)") (class "Default")
      (node (ref "P2") (pin "2") (pinfunction "2_2") (pintype "input"))
      (node (ref "Q2") (pin "3") (pinfunction "D_3") (pintype "unspecified"))
      (node (ref "R3") (pin "1") (pinfunction "1_1") (pintype "input"))
    )
    (net (code "21") (name "Net-(Q3-D)") (class "Default")
      (node (ref "P3") (pin "2") (pinfunction "2_2") (pintype "input"))
      (node (ref "Q3") (pin "3") (pinfunction "D_3") (pintype "unspecified"))
      (node (ref "R5") (pin "1") (pinfunction "1_1") (pintype "input"))
    )
    (net (code "22") (name "Net-(Q4-D)") (class "Default")
      (node (ref "P5") (pin "2") (pinfunction "2_2") (pintype "input"))
      (node (ref "Q4") (pin "3") (pinfunction "D_3") (pintype "unspecified"))
      (node (ref "R7") (pin "1") (pinfunction "1_1") (pintype "input"))
    )
    (net (code "23") (name "Net-(Q5-D)") (class "Default")
      (node (ref "P6") (pin "2") (pinfunction "2_2") (pintype "input"))
      (node (ref "Q5") (pin "3") (pinfunction "D_3") (pintype "unspecified"))
      (node (ref "R9") (pin "1") (pinfunction "1_1") (pintype "input"))
    )
    (net (code "24") (name "Net-(Q6-D)") (class "Default")
      (node (ref "P4") (pin "2") (pinfunction "2_2") (pintype "input"))
      (node (ref "Q6") (pin "3") (pinfunction "D_3") (pintype "unspecified"))
      (node (ref "R15") (pin "1") (pinfunction "1_1") (pintype "input"))
    )
    (net (code "25") (name "Net-(Q9-Pad1)") (class "Default")
      (node (ref "Q9") (pin "1") (pinfunction "1_1") (pintype "input"))
      (node (ref "R11") (pin "2") (pinfunction "2_2") (pintype "input"))
    )
    (net (code "26") (name "RTS") (class "Default")
      (node (ref "Q8") (pin "1") (pinfunction "1_1") (pintype "input"))
      (node (ref "Q9") (pin "2") (pinfunction "2_2") (pintype "input"))
      (node (ref "U20") (pin "14") (pinfunction "RTS#_14") (pintype "unspecified"))
    )
    (net (code "27") (name "RXD") (class "Default")
      (node (ref "LED2") (pin "4") (pinfunction "4_4") (pintype "unspecified"))
      (node (ref "U11") (pin "35") (pinfunction "TXD0_35") (pintype "unspecified"))
      (node (ref "U20") (pin "3") (pinfunction "RXD_3") (pintype "unspecified"))
    )
    (net (code "28") (name "RXp") (class "Default")
      (node (ref "U11") (pin "11") (pinfunction "IO26_11") (pintype "unspecified"))
      (node (ref "U2") (pin "3") (pinfunction "3_3") (pintype "unspecified"))
    )
    (net (code "29") (name "SCL") (class "Default")
      (node (ref "U1") (pin "3") (pinfunction "3_3") (pintype "unspecified"))
      (node (ref "U11") (pin "36") (pinfunction "IO22_36") (pintype "unspecified"))
      (node (ref "U8") (pin "3") (pinfunction "3_3") (pintype "unspecified"))
    )
    (net (code "30") (name "SDA") (class "Default")
      (node (ref "U1") (pin "2") (pinfunction "2_2") (pintype "unspecified"))
      (node (ref "U11") (pin "33") (pinfunction "IO21_33") (pintype "unspecified"))
      (node (ref "U8") (pin "2") (pinfunction "2_2") (pintype "unspecified"))
    )
    (net (code "31") (name "STRAIN1") (class "Default")
      (node (ref "U11") (pin "28") (pinfunction "IO17_28") (pintype "unspecified"))
      (node (ref "U9") (pin "3") (pinfunction "3_3") (pintype "unspecified"))
    )
    (net (code "32") (name "STRAIN2") (class "Default")
      (node (ref "U10") (pin "3") (pinfunction "3_3") (pintype "unspecified"))
      (node (ref "U11") (pin "27") (pinfunction "IO16_27") (pintype "unspecified"))
    )
    (net (code "33") (name "STRAIN3") (class "Default")
      (node (ref "U11") (pin "16") (pinfunction "IO13_16") (pintype "unspecified"))
      (node (ref "U12") (pin "3") (pinfunction "3_3") (pintype "unspecified"))
    )
    (net (code "34") (name "STRAIN4") (class "Default")
      (node (ref "U11") (pin "10") (pinfunction "IO25_10") (pintype "unspecified"))
      (node (ref "U14") (pin "3") (pinfunction "3_3") (pintype "unspecified"))
    )
    (net (code "35") (name "STRAIN5") (class "Default")
      (node (ref "U11") (pin "14") (pinfunction "IO12_14") (pintype "unspecified"))
      (node (ref "U16") (pin "3") (pinfunction "3_3") (pintype "unspecified"))
    )
    (net (code "36") (name "STRAIN6") (class "Default")
      (node (ref "U11") (pin "13") (pinfunction "IO14_13") (pintype "unspecified"))
      (node (ref "U18") (pin "3") (pinfunction "3_3") (pintype "unspecified"))
    )
    (net (code "37") (name "TXD") (class "Default")
      (node (ref "LED2") (pin "3") (pinfunction "3_3") (pintype "unspecified"))
      (node (ref "U11") (pin "34") (pinfunction "RXD0_34") (pintype "unspecified"))
      (node (ref "U20") (pin "2") (pinfunction "TXD_2") (pintype "unspecified"))
    )
    (net (code "38") (name "TXp") (class "Default")
      (node (ref "U11") (pin "12") (pinfunction "IO27_12") (pintype "unspecified"))
      (node (ref "U2") (pin "2") (pinfunction "2_2") (pintype "unspecified"))
    )
    (net (code "39") (name "neopixel") (class "Default")
      (node (ref "P7") (pin "2") (pinfunction "2_2") (pintype "input"))
      (node (ref "U11") (pin "23") (pinfunction "IO15_23") (pintype "unspecified"))
    )
    (net (code "40") (name "servo1") (class "Default")
      (node (ref "Q6") (pin "2") (pinfunction "S_2") (pintype "unspecified"))
      (node (ref "R14") (pin "1") (pinfunction "1_1") (pintype "input"))
      (node (ref "U11") (pin "9") (pinfunction "IO33_9") (pintype "unspecified"))
    )
    (net (code "41") (name "servo2") (class "Default")
      (node (ref "Q1") (pin "2") (pinfunction "S_2") (pintype "unspecified"))
      (node (ref "R2") (pin "1") (pinfunction "1_1") (pintype "input"))
      (node (ref "U11") (pin "8") (pinfunction "IO32_8") (pintype "unspecified"))
    )
    (net (code "42") (name "servo3") (class "Default")
      (node (ref "Q2") (pin "2") (pinfunction "S_2") (pintype "unspecified"))
      (node (ref "R4") (pin "1") (pinfunction "1_1") (pintype "input"))
      (node (ref "U11") (pin "31") (pinfunction "IO19_31") (pintype "unspecified"))
    )
    (net (code "43") (name "servo4") (class "Default")
      (node (ref "Q3") (pin "2") (pinfunction "S_2") (pintype "unspecified"))
      (node (ref "R6") (pin "1") (pinfunction "1_1") (pintype "input"))
      (node (ref "U11") (pin "26") (pinfunction "IO4_26") (pintype "unspecified"))
    )
    (net (code "44") (name "servo5") (class "Default")
      (node (ref "Q4") (pin "2") (pinfunction "S_2") (pintype "unspecified"))
      (node (ref "R8") (pin "1") (pinfunction "1_1") (pintype "input"))
      (node (ref "U11") (pin "37") (pinfunction "IO23_37") (pintype "unspecified"))
    )
    (net (code "45") (name "servo6") (class "Default")
      (node (ref "Q5") (pin "2") (pinfunction "S_2") (pintype "unspecified"))
      (node (ref "R10") (pin "1") (pinfunction "1_1") (pintype "input"))
      (node (ref "U11") (pin "30") (pinfunction "IO18_30") (pintype "unspecified"))
    )
    (net (code "46") (name "strainCLK") (class "Default")
      (node (ref "U10") (pin "2") (pinfunction "2_2") (pintype "unspecified"))
      (node (ref "U11") (pin "29") (pinfunction "IO5_29") (pintype "unspecified"))
      (node (ref "U12") (pin "2") (pinfunction "2_2") (pintype "unspecified"))
      (node (ref "U14") (pin "2") (pinfunction "2_2") (pintype "unspecified"))
      (node (ref "U16") (pin "2") (pinfunction "2_2") (pintype "unspecified"))
      (node (ref "U18") (pin "2") (pinfunction "2_2") (pintype "unspecified"))
      (node (ref "U9") (pin "2") (pinfunction "2_2") (pintype "unspecified"))
    )
    (net (code "47") (name "unconnected-(BOOT1-Pad3)") (class "Default")
      (node (ref "BOOT1") (pin "3") (pinfunction "3_3") (pintype "unspecified+no_connect"))
    )
    (net (code "48") (name "unconnected-(BOOT1-Pad4)") (class "Default")
      (node (ref "BOOT1") (pin "4") (pinfunction "4_4") (pintype "unspecified+no_connect"))
    )
    (net (code "49") (name "unconnected-(EN1-Pad3)") (class "Default")
      (node (ref "EN1") (pin "3") (pinfunction "3_3") (pintype "unspecified+no_connect"))
    )
    (net (code "50") (name "unconnected-(EN1-Pad4)") (class "Default")
      (node (ref "EN1") (pin "4") (pinfunction "4_4") (pintype "unspecified+no_connect"))
    )
    (net (code "51") (name "unconnected-(U11-IO2-Pad24)") (class "Default")
      (node (ref "U11") (pin "24") (pinfunction "IO2_24") (pintype "unspecified+no_connect"))
    )
    (net (code "52") (name "unconnected-(U11-IO34-Pad6)") (class "Default")
      (node (ref "U11") (pin "6") (pinfunction "IO34_6") (pintype "unspecified+no_connect"))
    )
    (net (code "53") (name "unconnected-(U11-IO35-Pad7)") (class "Default")
      (node (ref "U11") (pin "7") (pinfunction "IO35_7") (pintype "unspecified+no_connect"))
    )
    (net (code "54") (name "unconnected-(U11-NC-Pad17)") (class "Default")
      (node (ref "U11") (pin "17") (pinfunction "NC_17") (pintype "unspecified+no_connect"))
    )
    (net (code "55") (name "unconnected-(U11-NC-Pad18)") (class "Default")
      (node (ref "U11") (pin "18") (pinfunction "NC_18") (pintype "unspecified+no_connect"))
    )
    (net (code "56") (name "unconnected-(U11-NC-Pad19)") (class "Default")
      (node (ref "U11") (pin "19") (pinfunction "NC_19") (pintype "unspecified+no_connect"))
    )
    (net (code "57") (name "unconnected-(U11-NC-Pad20)") (class "Default")
      (node (ref "U11") (pin "20") (pinfunction "NC_20") (pintype "unspecified+no_connect"))
    )
    (net (code "58") (name "unconnected-(U11-NC-Pad21)") (class "Default")
      (node (ref "U11") (pin "21") (pinfunction "NC_21") (pintype "unspecified+no_connect"))
    )
    (net (code "59") (name "unconnected-(U11-NC-Pad22)") (class "Default")
      (node (ref "U11") (pin "22") (pinfunction "NC_22") (pintype "unspecified+no_connect"))
    )
    (net (code "60") (name "unconnected-(U11-NC-Pad32)") (class "Default")
      (node (ref "U11") (pin "32") (pinfunction "NC_32") (pintype "unspecified+no_connect"))
    )
    (net (code "61") (name "unconnected-(U11-SENSOR_VN-Pad5)") (class "Default")
      (node (ref "U11") (pin "5") (pinfunction "SENSOR_VN_5") (pintype "unspecified+no_connect"))
    )
    (net (code "62") (name "unconnected-(U11-SENSOR_VP-Pad4)") (class "Default")
      (node (ref "U11") (pin "4") (pinfunction "SENSOR_VP_4") (pintype "unspecified+no_connect"))
    )
    (net (code "63") (name "unconnected-(U20-CTS#-Pad9)") (class "Default")
      (node (ref "U20") (pin "9") (pinfunction "CTS#_9") (pintype "unspecified+no_connect"))
    )
    (net (code "64") (name "unconnected-(U20-DCD#-Pad12)") (class "Default")
      (node (ref "U20") (pin "12") (pinfunction "DCD#_12") (pintype "unspecified+no_connect"))
    )
    (net (code "65") (name "unconnected-(U20-DSR#-Pad10)") (class "Default")
      (node (ref "U20") (pin "10") (pinfunction "DSR#_10") (pintype "unspecified+no_connect"))
    )
    (net (code "66") (name "unconnected-(U20-NC.-Pad7)") (class "Default")
      (node (ref "U20") (pin "7") (pinfunction "NC._7") (pintype "unspecified+no_connect"))
    )
    (net (code "67") (name "unconnected-(U20-NC.-Pad8)") (class "Default")
      (node (ref "U20") (pin "8") (pinfunction "NC._8") (pintype "unspecified+no_connect"))
    )
    (net (code "68") (name "unconnected-(U20-R232-Pad15)") (class "Default")
      (node (ref "U20") (pin "15") (pinfunction "R232_15") (pintype "unspecified+no_connect"))
    )
    (net (code "69") (name "unconnected-(U20-RI#-Pad11)") (class "Default")
      (node (ref "U20") (pin "11") (pinfunction "RI#_11") (pintype "unspecified+no_connect"))
    )
    (net (code "70") (name "unconnected-(U21-VOUT(TAB)-Pad2)") (class "Default")
      (node (ref "U21") (pin "2") (pinfunction "VOUT(TAB)_2") (pintype "unspecified+no_connect"))
    )
    (net (code "71") (name "unconnected-(USB1-SBU1-PadA8)") (class "Default")
      (node (ref "USB1") (pin "A8") (pinfunction "SBU1_A8") (pintype "unspecified+no_connect"))
    )
    (net (code "72") (name "unconnected-(USB1-SBU2-PadB8)") (class "Default")
      (node (ref "USB1") (pin "B8") (pinfunction "SBU2_B8") (pintype "unspecified+no_connect"))
    )
  )
)
